# LoRa_Node_Schematic.net
KiCad netlist of a schematic drawn in EAGLE
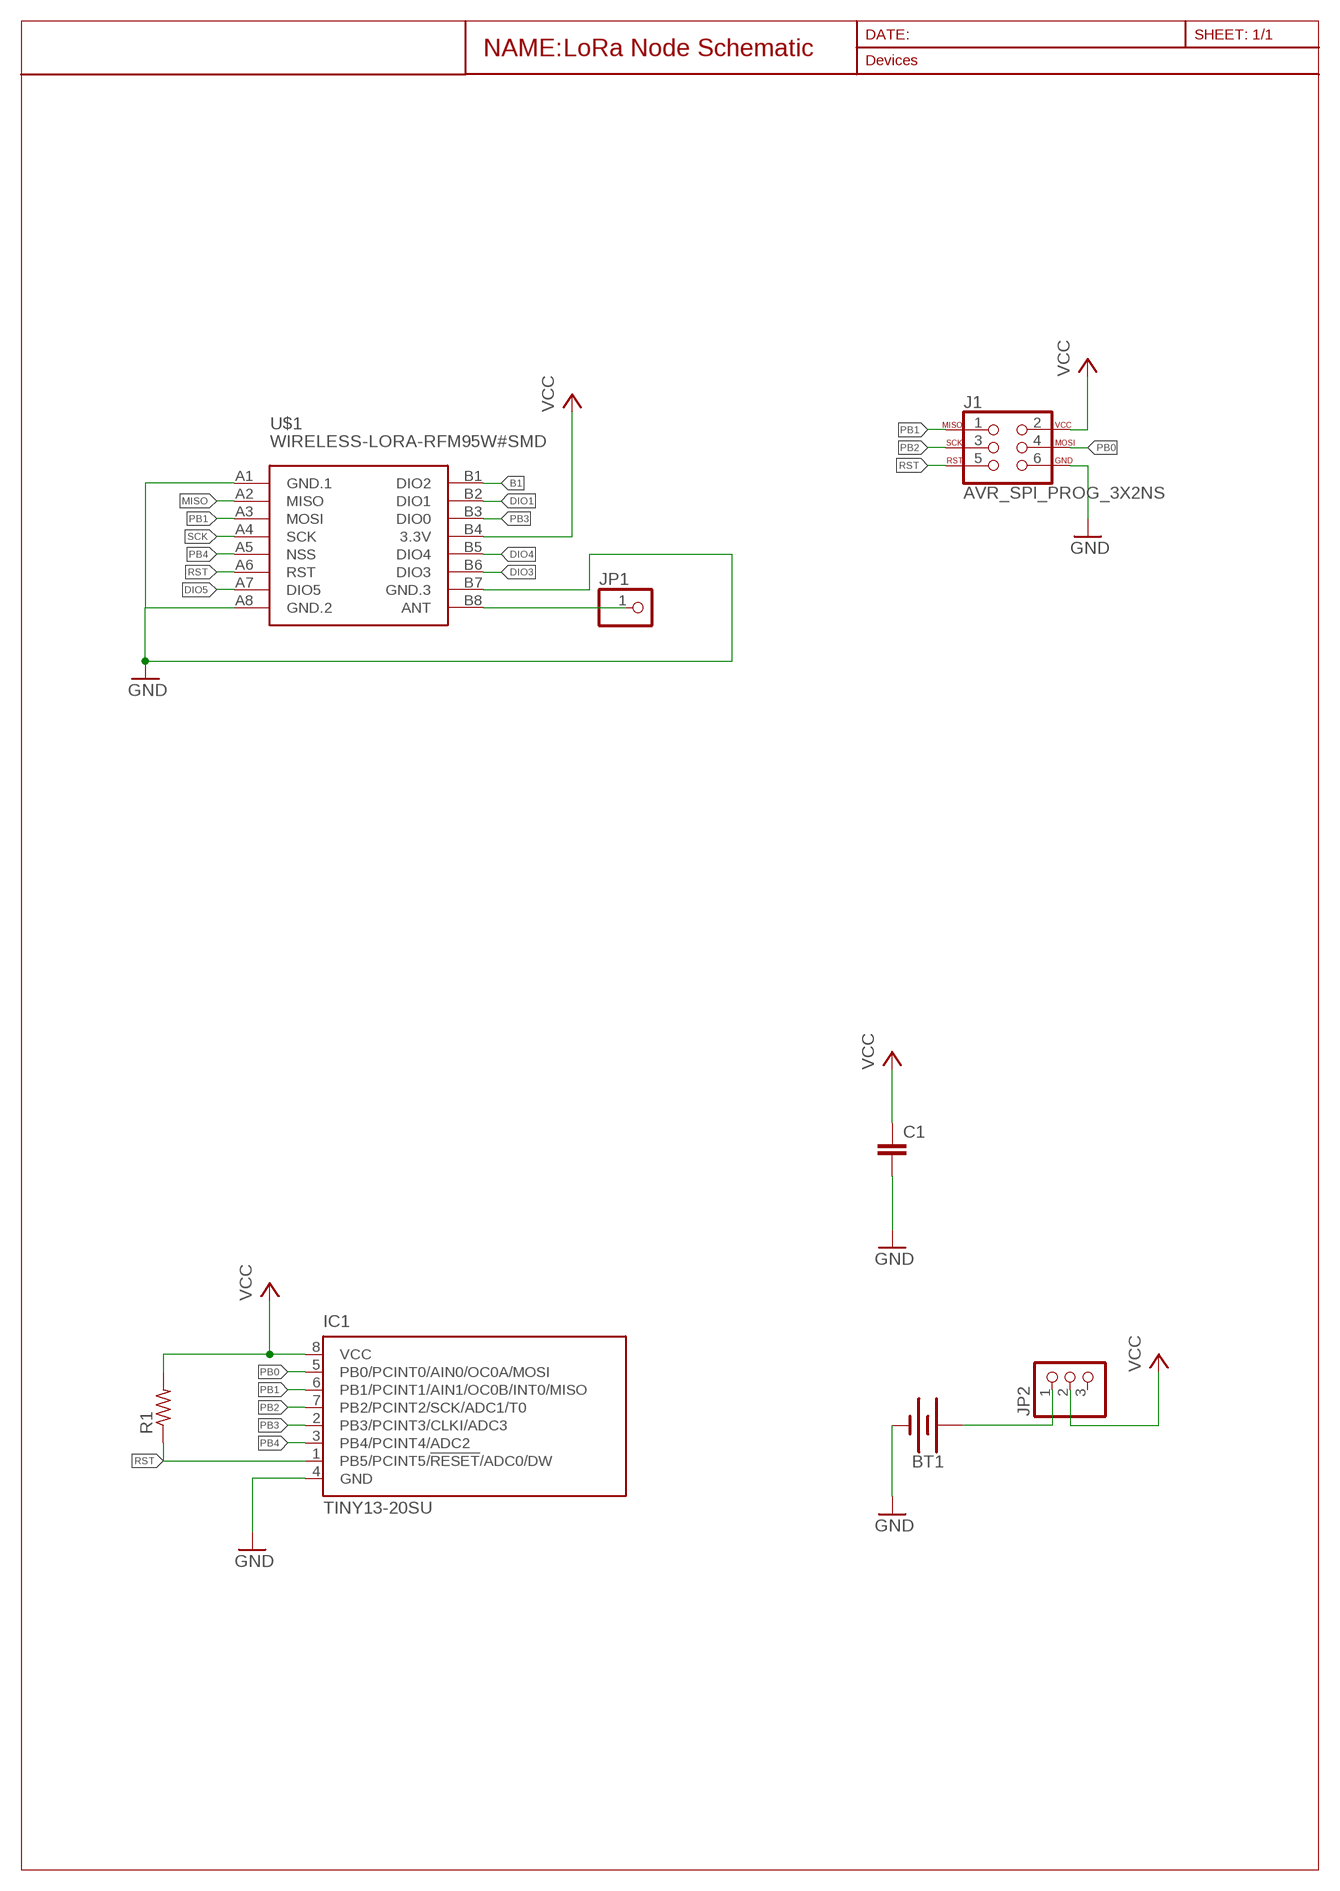
[diagram p0: schematic, sheet 1]

(export (version "E")
  (design (tool "Eeschema 10.0.6"))
  (components
    (comp (ref "BT1")
      (value "BATTERY-20MM_PTH")
      (footprint "eagle-import:BATTCOM_20MM_PTH")
      (libsource (lib "eagle-import") (part "BATTERY-20MM_PTH"))
    )
    (comp (ref "C1")
      (value "C-EUC0603")
      (footprint "eagle-import:C0603")
      (libsource (lib "eagle-import") (part "C-EUC0603"))
    )
    (comp (ref "IC1")
      (value "TINY13-20SU")
      (footprint "eagle-import:8S2")
      (fields (field (name "MPN") "ATTINY13-20SU"))
      (libsource (lib "eagle-import") (part "TINY13SU-20"))
    )
    (comp (ref "J1")
      (value "AVR_SPI_PROG_3X2NS")
      (footprint "eagle-import:2X3-NS")
      (libsource (lib "eagle-import") (part "AVR_SPI_PROG_3X2NS"))
    )
    (comp (ref "JP1")
      (value "PINHD-1X1CB")
      (footprint "eagle-import:1X01-CLEANBIG")
      (libsource (lib "eagle-import") (part "PINHD-1X1CB"))
    )
    (comp (ref "JP2")
      (value "PINHD-1X3")
      (footprint "eagle-import:1X03")
      (libsource (lib "eagle-import") (part "PINHD-1X3"))
    )
    (comp (ref "R1")
      (value "R-US_R0603")
      (footprint "eagle-import:R0603")
      (libsource (lib "eagle-import") (part "R-US_R0603"))
    )
    (comp (ref "U$1")
      (value "WIRELESS-LORA-RFM95W#SMD")
      (footprint "eagle-import:WIRELESS-LORA-RFM95W#SMD")
      (libsource (lib "eagle-import") (part "WIRELESS-LORA-RFM95W#SMD"))
    )
  )
  (nets
    (net (code "1") (name "B1") (class "Default")
      (node (ref "U$1") (pin "B1") (pinfunction "DIO2_B1") (pintype "bidirectional"))
    )
    (net (code "2") (name "DIO1") (class "Default")
      (node (ref "U$1") (pin "B2") (pinfunction "DIO1_B2") (pintype "bidirectional"))
    )
    (net (code "3") (name "DIO3") (class "Default")
      (node (ref "U$1") (pin "B6") (pinfunction "DIO3_B6") (pintype "bidirectional"))
    )
    (net (code "4") (name "DIO4") (class "Default")
      (node (ref "U$1") (pin "B5") (pinfunction "DIO4_B5") (pintype "bidirectional"))
    )
    (net (code "5") (name "DIO5") (class "Default")
      (node (ref "U$1") (pin "A7") (pinfunction "DIO5_A7") (pintype "bidirectional"))
    )
    (net (code "6") (name "GND") (class "Default")
      (node (ref "BT1") (pin "2") (pinfunction "-_2") (pintype "power_in"))
      (node (ref "C1") (pin "2") (pinfunction "2_2") (pintype "passive"))
      (node (ref "IC1") (pin "4") (pinfunction "GND_4") (pintype "power_in"))
      (node (ref "J1") (pin "6") (pinfunction "6_6") (pintype "passive"))
      (node (ref "U$1") (pin "A1") (pinfunction "GND.1_A1") (pintype "power_in"))
      (node (ref "U$1") (pin "A8") (pinfunction "GND.2_A8") (pintype "power_in"))
      (node (ref "U$1") (pin "B7") (pinfunction "GND.3_B7") (pintype "power_in"))
    )
    (net (code "7") (name "MISO") (class "Default")
      (node (ref "U$1") (pin "A2") (pinfunction "MISO_A2") (pintype "bidirectional"))
    )
    (net (code "8") (name "Net-(BT1-+)") (class "Default")
      (node (ref "BT1") (pin "1") (pinfunction "+_1") (pintype "power_in"))
      (node (ref "JP2") (pin "1") (pinfunction "1_1") (pintype "passive"))
    )
    (net (code "9") (name "Net-(U$1-ANT)") (class "Default")
      (node (ref "JP1") (pin "1") (pinfunction "1_1") (pintype "passive"))
      (node (ref "U$1") (pin "B8") (pinfunction "ANT_B8") (pintype "passive"))
    )
    (net (code "10") (name "PB0") (class "Default")
      (node (ref "IC1") (pin "5") (pinfunction "PB0/PCINT0/AIN0/OC0A/MOSI_5") (pintype "bidirectional"))
      (node (ref "J1") (pin "4") (pinfunction "4_4") (pintype "passive"))
    )
    (net (code "11") (name "PB1") (class "Default")
      (node (ref "IC1") (pin "6") (pinfunction "PB1/PCINT1/AIN1/OC0B/INT0/MISO_6") (pintype "bidirectional"))
      (node (ref "J1") (pin "1") (pinfunction "1_1") (pintype "passive"))
      (node (ref "U$1") (pin "A3") (pinfunction "MOSI_A3") (pintype "bidirectional"))
    )
    (net (code "12") (name "PB2") (class "Default")
      (node (ref "IC1") (pin "7") (pinfunction "PB2/PCINT2/SCK/ADC1/T0_7") (pintype "bidirectional"))
      (node (ref "J1") (pin "3") (pinfunction "3_3") (pintype "passive"))
    )
    (net (code "13") (name "PB3") (class "Default")
      (node (ref "IC1") (pin "2") (pinfunction "PB3/PCINT3/CLKI/ADC3_2") (pintype "bidirectional"))
      (node (ref "U$1") (pin "B3") (pinfunction "DIO0_B3") (pintype "bidirectional"))
    )
    (net (code "14") (name "PB4") (class "Default")
      (node (ref "IC1") (pin "3") (pinfunction "PB4/PCINT4/ADC2_3") (pintype "bidirectional"))
      (node (ref "U$1") (pin "A5") (pinfunction "NSS_A5") (pintype "bidirectional"))
    )
    (net (code "15") (name "RST") (class "Default")
      (node (ref "IC1") (pin "1") (pinfunction "PB5/PCINT5/~{RESET}/ADC0/DW_1") (pintype "bidirectional"))
      (node (ref "J1") (pin "5") (pinfunction "5_5") (pintype "passive"))
      (node (ref "R1") (pin "1") (pinfunction "1_1") (pintype "passive"))
      (node (ref "U$1") (pin "A6") (pinfunction "RST_A6") (pintype "bidirectional"))
    )
    (net (code "16") (name "SCK") (class "Default")
      (node (ref "U$1") (pin "A4") (pinfunction "SCK_A4") (pintype "bidirectional"))
    )
    (net (code "17") (name "VCC") (class "Default")
      (node (ref "C1") (pin "1") (pinfunction "1_1") (pintype "passive"))
      (node (ref "IC1") (pin "8") (pinfunction "VCC_8") (pintype "power_in"))
      (node (ref "J1") (pin "2") (pinfunction "2_2") (pintype "passive"))
      (node (ref "JP2") (pin "2") (pinfunction "2_2") (pintype "passive"))
      (node (ref "R1") (pin "2") (pinfunction "2_2") (pintype "passive"))
      (node (ref "U$1") (pin "B4") (pinfunction "3.3V_B4") (pintype "power_in"))
    )
    (net (code "18") (name "unconnected-(JP2-Pad3)") (class "Default")
      (node (ref "JP2") (pin "3") (pinfunction "3_3") (pintype "passive"))
    )
  )
)
